# IMX_1_2V_Digital_Power_Supply.net
KiCad netlist of a schematic drawn in Altium Designer
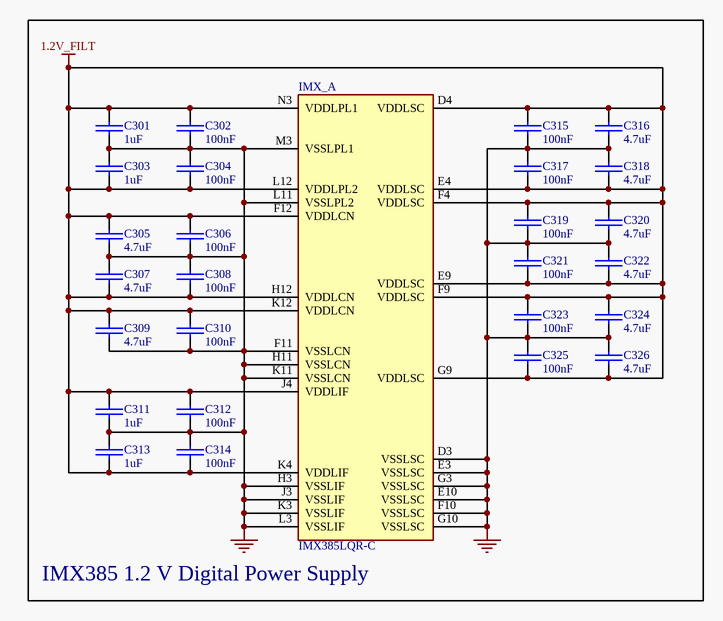
[diagram p0: IMX_1.2V Digital Power Supply.SchDoc]

(export (version "E")
  (design (tool "Eeschema 10.0.6"))
  (components
    (comp (ref "C301")
      (value "1uF")
      (footprint "Capacitor, 0402")
      (description "Ceramic Capacitor, 10V, 10% +/- Tol, X7R, 1uF, SMD, 0402, #GRM155Z71A105KE01D, JLC#C528974")
      (libsource (lib "Component Library") (part "Capacitor, 0402, 1uF"))
    )
    (comp (ref "C302")
      (value "100nF")
      (footprint "Capacitor, 0402")
      (description "Ceramic Capacitor, 16V, 10% +/- Tol, X7R, 0.1uF, SMD, 0402, #CL05B104KO5NNNC, JLC#C1525")
      (libsource (lib "Component Library") (part "Capacitor, 0402, 100nF"))
    )
    (comp (ref "C303")
      (value "1uF")
      (footprint "Capacitor, 0402")
      (description "Ceramic Capacitor, 10V, 10% +/- Tol, X7R, 1uF, SMD, 0402, #GRM155Z71A105KE01D, JLC#C528974")
      (libsource (lib "Component Library") (part "Capacitor, 0402, 1uF"))
    )
    (comp (ref "C304")
      (value "100nF")
      (footprint "Capacitor, 0402")
      (description "Ceramic Capacitor, 16V, 10% +/- Tol, X7R, 0.1uF, SMD, 0402, #CL05B104KO5NNNC, JLC#C1525")
      (libsource (lib "Component Library") (part "Capacitor, 0402, 100nF"))
    )
    (comp (ref "C305")
      (value "4.7uF")
      (footprint "Capacitor, 0402")
      (description "Ceramic Capacitor, 10V, 10% +/- Tol, X5R, 4.7uF, SMD, 0402, #CL05A475KP5NRNC, JLC#C368809")
      (libsource (lib "Component Library") (part "Capacitor, 0402, 4.7uF"))
    )
    (comp (ref "C306")
      (value "100nF")
      (footprint "Capacitor, 0402")
      (description "Ceramic Capacitor, 16V, 10% +/- Tol, X7R, 0.1uF, SMD, 0402, #CL05B104KO5NNNC, JLC#C1525")
      (libsource (lib "Component Library") (part "Capacitor, 0402, 100nF"))
    )
    (comp (ref "C307")
      (value "4.7uF")
      (footprint "Capacitor, 0402")
      (description "Ceramic Capacitor, 10V, 10% +/- Tol, X5R, 4.7uF, SMD, 0402, #CL05A475KP5NRNC, JLC#C368809")
      (libsource (lib "Component Library") (part "Capacitor, 0402, 4.7uF"))
    )
    (comp (ref "C308")
      (value "100nF")
      (footprint "Capacitor, 0402")
      (description "Ceramic Capacitor, 16V, 10% +/- Tol, X7R, 0.1uF, SMD, 0402, #CL05B104KO5NNNC, JLC#C1525")
      (libsource (lib "Component Library") (part "Capacitor, 0402, 100nF"))
    )
    (comp (ref "C309")
      (value "4.7uF")
      (footprint "Capacitor, 0402")
      (description "Ceramic Capacitor, 10V, 10% +/- Tol, X5R, 4.7uF, SMD, 0402, #CL05A475KP5NRNC, JLC#C368809")
      (libsource (lib "Component Library") (part "Capacitor, 0402, 4.7uF"))
    )
    (comp (ref "C310")
      (value "100nF")
      (footprint "Capacitor, 0402")
      (description "Ceramic Capacitor, 16V, 10% +/- Tol, X7R, 0.1uF, SMD, 0402, #CL05B104KO5NNNC, JLC#C1525")
      (libsource (lib "Component Library") (part "Capacitor, 0402, 100nF"))
    )
    (comp (ref "C311")
      (value "1uF")
      (footprint "Capacitor, 0402")
      (description "Ceramic Capacitor, 10V, 10% +/- Tol, X7R, 1uF, SMD, 0402, #GRM155Z71A105KE01D, JLC#C528974")
      (libsource (lib "Component Library") (part "Capacitor, 0402, 1uF"))
    )
    (comp (ref "C312")
      (value "100nF")
      (footprint "Capacitor, 0402")
      (description "Ceramic Capacitor, 16V, 10% +/- Tol, X7R, 0.1uF, SMD, 0402, #CL05B104KO5NNNC, JLC#C1525")
      (libsource (lib "Component Library") (part "Capacitor, 0402, 100nF"))
    )
    (comp (ref "C313")
      (value "1uF")
      (footprint "Capacitor, 0402")
      (description "Ceramic Capacitor, 10V, 10% +/- Tol, X7R, 1uF, SMD, 0402, #GRM155Z71A105KE01D, JLC#C528974")
      (libsource (lib "Component Library") (part "Capacitor, 0402, 1uF"))
    )
    (comp (ref "C314")
      (value "100nF")
      (footprint "Capacitor, 0402")
      (description "Ceramic Capacitor, 16V, 10% +/- Tol, X7R, 0.1uF, SMD, 0402, #CL05B104KO5NNNC, JLC#C1525")
      (libsource (lib "Component Library") (part "Capacitor, 0402, 100nF"))
    )
    (comp (ref "C315")
      (value "100nF")
      (footprint "Capacitor, 0402")
      (description "Ceramic Capacitor, 16V, 10% +/- Tol, X7R, 0.1uF, SMD, 0402, #CL05B104KO5NNNC, JLC#C1525")
      (libsource (lib "Component Library") (part "Capacitor, 0402, 100nF"))
    )
    (comp (ref "C316")
      (value "4.7uF")
      (footprint "Capacitor, 0402")
      (description "Ceramic Capacitor, 10V, 10% +/- Tol, X5R, 4.7uF, SMD, 0402, #CL05A475KP5NRNC, JLC#C368809")
      (libsource (lib "Component Library") (part "Capacitor, 0402, 4.7uF"))
    )
    (comp (ref "C317")
      (value "100nF")
      (footprint "Capacitor, 0402")
      (description "Ceramic Capacitor, 16V, 10% +/- Tol, X7R, 0.1uF, SMD, 0402, #CL05B104KO5NNNC, JLC#C1525")
      (libsource (lib "Component Library") (part "Capacitor, 0402, 100nF"))
    )
    (comp (ref "C318")
      (value "4.7uF")
      (footprint "Capacitor, 0402")
      (description "Ceramic Capacitor, 10V, 10% +/- Tol, X5R, 4.7uF, SMD, 0402, #CL05A475KP5NRNC, JLC#C368809")
      (libsource (lib "Component Library") (part "Capacitor, 0402, 4.7uF"))
    )
    (comp (ref "C319")
      (value "100nF")
      (footprint "Capacitor, 0402")
      (description "Ceramic Capacitor, 16V, 10% +/- Tol, X7R, 0.1uF, SMD, 0402, #CL05B104KO5NNNC, JLC#C1525")
      (libsource (lib "Component Library") (part "Capacitor, 0402, 100nF"))
    )
    (comp (ref "C320")
      (value "4.7uF")
      (footprint "Capacitor, 0402")
      (description "Ceramic Capacitor, 10V, 10% +/- Tol, X5R, 4.7uF, SMD, 0402, #CL05A475KP5NRNC, JLC#C368809")
      (libsource (lib "Component Library") (part "Capacitor, 0402, 4.7uF"))
    )
    (comp (ref "C321")
      (value "100nF")
      (footprint "Capacitor, 0402")
      (description "Ceramic Capacitor, 16V, 10% +/- Tol, X7R, 0.1uF, SMD, 0402, #CL05B104KO5NNNC, JLC#C1525")
      (libsource (lib "Component Library") (part "Capacitor, 0402, 100nF"))
    )
    (comp (ref "C322")
      (value "4.7uF")
      (footprint "Capacitor, 0402")
      (description "Ceramic Capacitor, 10V, 10% +/- Tol, X5R, 4.7uF, SMD, 0402, #CL05A475KP5NRNC, JLC#C368809")
      (libsource (lib "Component Library") (part "Capacitor, 0402, 4.7uF"))
    )
    (comp (ref "C323")
      (value "100nF")
      (footprint "Capacitor, 0402")
      (description "Ceramic Capacitor, 16V, 10% +/- Tol, X7R, 0.1uF, SMD, 0402, #CL05B104KO5NNNC, JLC#C1525")
      (libsource (lib "Component Library") (part "Capacitor, 0402, 100nF"))
    )
    (comp (ref "C324")
      (value "4.7uF")
      (footprint "Capacitor, 0402")
      (description "Ceramic Capacitor, 10V, 10% +/- Tol, X5R, 4.7uF, SMD, 0402, #CL05A475KP5NRNC, JLC#C368809")
      (libsource (lib "Component Library") (part "Capacitor, 0402, 4.7uF"))
    )
    (comp (ref "C325")
      (value "100nF")
      (footprint "Capacitor, 0402")
      (description "Ceramic Capacitor, 16V, 10% +/- Tol, X7R, 0.1uF, SMD, 0402, #CL05B104KO5NNNC, JLC#C1525")
      (libsource (lib "Component Library") (part "Capacitor, 0402, 100nF"))
    )
    (comp (ref "C326")
      (value "4.7uF")
      (footprint "Capacitor, 0402")
      (description "Ceramic Capacitor, 10V, 10% +/- Tol, X5R, 4.7uF, SMD, 0402, #CL05A475KP5NRNC, JLC#C368809")
      (libsource (lib "Component Library") (part "Capacitor, 0402, 4.7uF"))
    )
    (comp (ref "IMX_")
      (value "IMX385LQR-C")
      (footprint "IMX385LQR")
      (libsource (lib "Component Library") (part "IMX385LQR"))
    )
  )
  (nets
    (net (code "1") (name "1.2V_FILT") (class "Default")
      (node (ref "C301") (pin "1") (pinfunction "1_1") (pintype "passive"))
      (node (ref "C302") (pin "1") (pinfunction "1_1") (pintype "passive"))
      (node (ref "C303") (pin "2") (pinfunction "2_2") (pintype "passive"))
      (node (ref "C304") (pin "2") (pinfunction "2_2") (pintype "passive"))
      (node (ref "C305") (pin "1") (pinfunction "1_1") (pintype "passive"))
      (node (ref "C306") (pin "1") (pinfunction "1_1") (pintype "passive"))
      (node (ref "C307") (pin "2") (pinfunction "2_2") (pintype "passive"))
      (node (ref "C308") (pin "2") (pinfunction "2_2") (pintype "passive"))
      (node (ref "C309") (pin "1") (pinfunction "1_1") (pintype "passive"))
      (node (ref "C310") (pin "1") (pinfunction "1_1") (pintype "passive"))
      (node (ref "C311") (pin "1") (pinfunction "1_1") (pintype "passive"))
      (node (ref "C312") (pin "1") (pinfunction "1_1") (pintype "passive"))
      (node (ref "C313") (pin "2") (pinfunction "2_2") (pintype "passive"))
      (node (ref "C314") (pin "2") (pinfunction "2_2") (pintype "passive"))
      (node (ref "C315") (pin "1") (pinfunction "1_1") (pintype "passive"))
      (node (ref "C316") (pin "1") (pinfunction "1_1") (pintype "passive"))
      (node (ref "C317") (pin "2") (pinfunction "2_2") (pintype "passive"))
      (node (ref "C318") (pin "2") (pinfunction "2_2") (pintype "passive"))
      (node (ref "C319") (pin "1") (pinfunction "1_1") (pintype "passive"))
      (node (ref "C320") (pin "1") (pinfunction "1_1") (pintype "passive"))
      (node (ref "C321") (pin "2") (pinfunction "2_2") (pintype "passive"))
      (node (ref "C322") (pin "2") (pinfunction "2_2") (pintype "passive"))
      (node (ref "C323") (pin "1") (pinfunction "1_1") (pintype "passive"))
      (node (ref "C324") (pin "1") (pinfunction "1_1") (pintype "passive"))
      (node (ref "C325") (pin "2") (pinfunction "2_2") (pintype "passive"))
      (node (ref "C326") (pin "2") (pinfunction "2_2") (pintype "passive"))
      (node (ref "IMX_") (pin "D4") (pinfunction "VDDLSC_D4") (pintype "passive"))
      (node (ref "IMX_") (pin "E4") (pinfunction "VDDLSC_E4") (pintype "passive"))
      (node (ref "IMX_") (pin "E9") (pinfunction "VDDLSC_E9") (pintype "passive"))
      (node (ref "IMX_") (pin "F12") (pinfunction "VDDLCN_F12") (pintype "passive"))
      (node (ref "IMX_") (pin "F4") (pinfunction "VDDLSC_F4") (pintype "passive"))
      (node (ref "IMX_") (pin "F9") (pinfunction "VDDLSC_F9") (pintype "passive"))
      (node (ref "IMX_") (pin "G9") (pinfunction "VDDLSC_G9") (pintype "passive"))
      (node (ref "IMX_") (pin "H12") (pinfunction "VDDLCN_H12") (pintype "passive"))
      (node (ref "IMX_") (pin "J4") (pinfunction "VDDLIF_J4") (pintype "passive"))
      (node (ref "IMX_") (pin "K12") (pinfunction "VDDLCN_K12") (pintype "passive"))
      (node (ref "IMX_") (pin "K4") (pinfunction "VDDLIF_K4") (pintype "passive"))
      (node (ref "IMX_") (pin "L12") (pinfunction "VDDLPL2_L12") (pintype "passive"))
      (node (ref "IMX_") (pin "N3") (pinfunction "VDDLPL1_N3") (pintype "passive"))
    )
    (net (code "2") (name "GND") (class "Default")
      (node (ref "C301") (pin "2") (pinfunction "2_2") (pintype "passive"))
      (node (ref "C302") (pin "2") (pinfunction "2_2") (pintype "passive"))
      (node (ref "C303") (pin "1") (pinfunction "1_1") (pintype "passive"))
      (node (ref "C304") (pin "1") (pinfunction "1_1") (pintype "passive"))
      (node (ref "C305") (pin "2") (pinfunction "2_2") (pintype "passive"))
      (node (ref "C306") (pin "2") (pinfunction "2_2") (pintype "passive"))
      (node (ref "C307") (pin "1") (pinfunction "1_1") (pintype "passive"))
      (node (ref "C308") (pin "1") (pinfunction "1_1") (pintype "passive"))
      (node (ref "C309") (pin "2") (pinfunction "2_2") (pintype "passive"))
      (node (ref "C310") (pin "2") (pinfunction "2_2") (pintype "passive"))
      (node (ref "C311") (pin "2") (pinfunction "2_2") (pintype "passive"))
      (node (ref "C312") (pin "2") (pinfunction "2_2") (pintype "passive"))
      (node (ref "C313") (pin "1") (pinfunction "1_1") (pintype "passive"))
      (node (ref "C314") (pin "1") (pinfunction "1_1") (pintype "passive"))
      (node (ref "C315") (pin "2") (pinfunction "2_2") (pintype "passive"))
      (node (ref "C316") (pin "2") (pinfunction "2_2") (pintype "passive"))
      (node (ref "C317") (pin "1") (pinfunction "1_1") (pintype "passive"))
      (node (ref "C318") (pin "1") (pinfunction "1_1") (pintype "passive"))
      (node (ref "C319") (pin "2") (pinfunction "2_2") (pintype "passive"))
      (node (ref "C320") (pin "2") (pinfunction "2_2") (pintype "passive"))
      (node (ref "C321") (pin "1") (pinfunction "1_1") (pintype "passive"))
      (node (ref "C322") (pin "1") (pinfunction "1_1") (pintype "passive"))
      (node (ref "C323") (pin "2") (pinfunction "2_2") (pintype "passive"))
      (node (ref "C324") (pin "2") (pinfunction "2_2") (pintype "passive"))
      (node (ref "C325") (pin "1") (pinfunction "1_1") (pintype "passive"))
      (node (ref "C326") (pin "1") (pinfunction "1_1") (pintype "passive"))
      (node (ref "IMX_") (pin "D3") (pinfunction "VSSLSC_D3") (pintype "passive"))
      (node (ref "IMX_") (pin "E10") (pinfunction "VSSLSC_E10") (pintype "passive"))
      (node (ref "IMX_") (pin "E3") (pinfunction "VSSLSC_E3") (pintype "passive"))
      (node (ref "IMX_") (pin "F10") (pinfunction "VSSLSC_F10") (pintype "passive"))
      (node (ref "IMX_") (pin "F11") (pinfunction "VSSLCN_F11") (pintype "passive"))
      (node (ref "IMX_") (pin "G10") (pinfunction "VSSLSC_G10") (pintype "passive"))
      (node (ref "IMX_") (pin "G3") (pinfunction "VSSLSC_G3") (pintype "passive"))
      (node (ref "IMX_") (pin "H11") (pinfunction "VSSLCN_H11") (pintype "passive"))
      (node (ref "IMX_") (pin "H3") (pinfunction "VSSLIF_H3") (pintype "passive"))
      (node (ref "IMX_") (pin "J3") (pinfunction "VSSLIF_J3") (pintype "passive"))
      (node (ref "IMX_") (pin "K11") (pinfunction "VSSLCN_K11") (pintype "passive"))
      (node (ref "IMX_") (pin "K3") (pinfunction "VSSLIF_K3") (pintype "passive"))
      (node (ref "IMX_") (pin "L11") (pinfunction "VSSLPL2_L11") (pintype "passive"))
      (node (ref "IMX_") (pin "L3") (pinfunction "VSSLIF_L3") (pintype "passive"))
      (node (ref "IMX_") (pin "M3") (pinfunction "VSSLPL1_M3") (pintype "passive"))
    )
  )
)
